# ersa_schematics_analog.net
KiCad netlist of a schematic drawn in Altium Designer
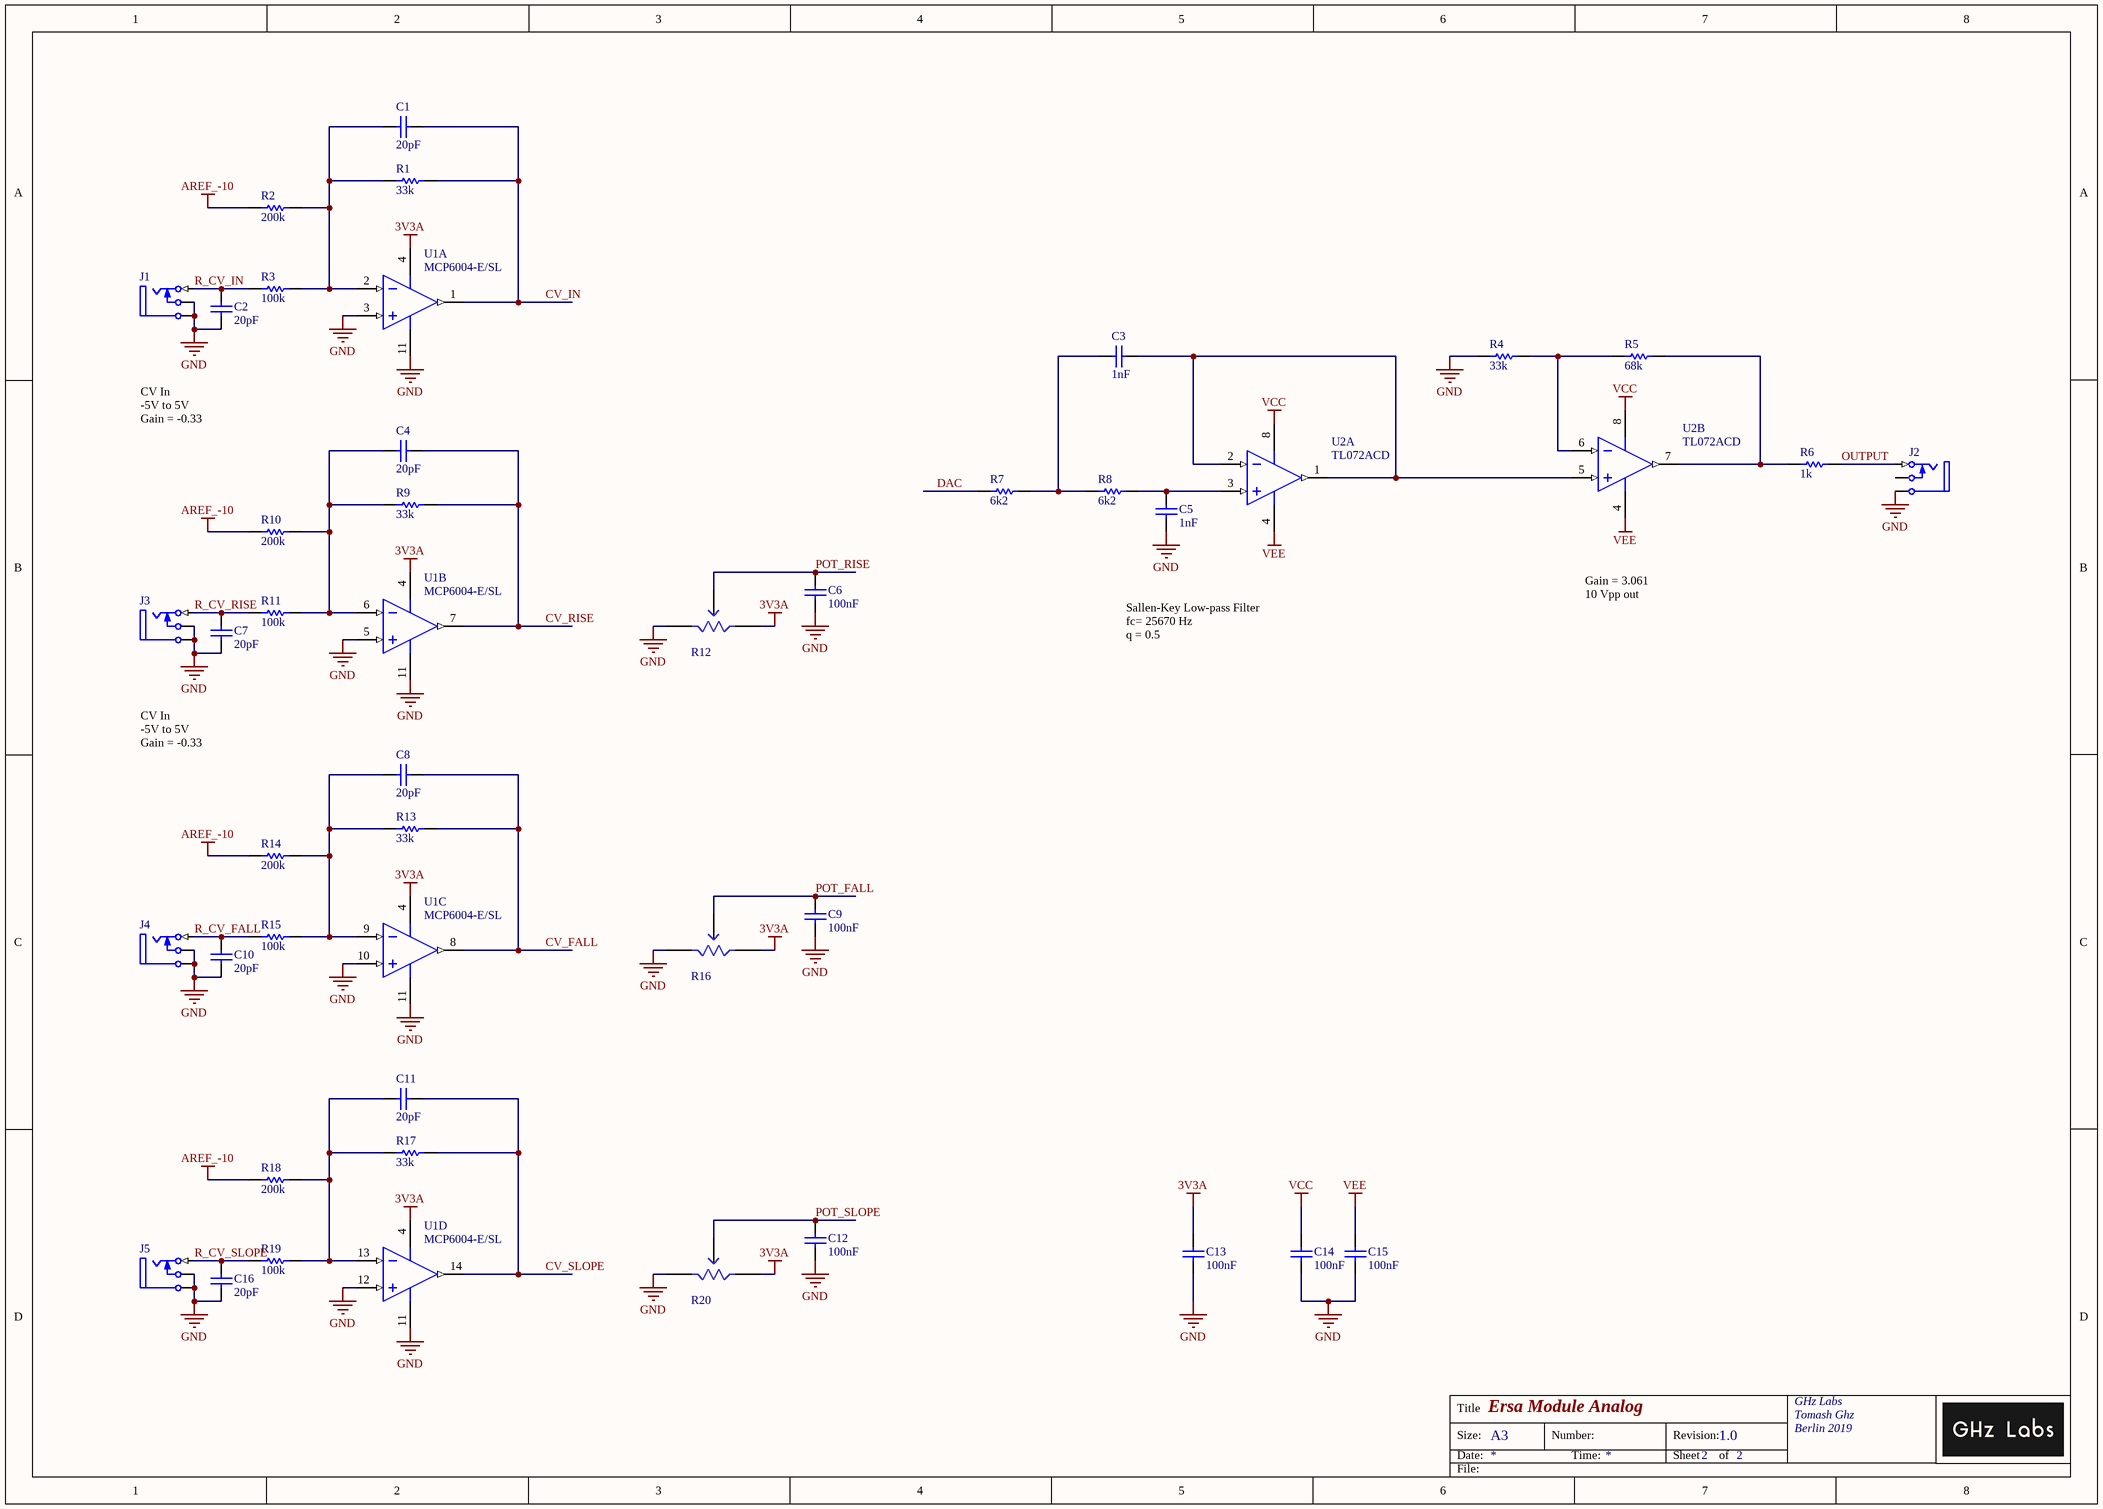
[diagram p0: ersa_schematics_analog.SchDoc]

(export (version "E")
  (design (tool "Eeschema 10.0.6"))
  (components
    (comp (ref "C1")
      (value "20pF")
      (footprint "GHzLabs_Parts:CAPA_0805")
      (description "Capacitor")
      (fields (field (name "PUBLISHER") "Altium Limited"))
      (libsource (lib "GHzLabs_Parts") (part "Cap"))
    )
    (comp (ref "C2")
      (value "20pF")
      (footprint "GHzLabs_Parts:CAPA_0805")
      (description "Capacitor")
      (fields (field (name "PUBLISHER") "Altium Limited"))
      (libsource (lib "GHzLabs_Parts") (part "Cap"))
    )
    (comp (ref "C3")
      (value "1nF")
      (footprint "GHzLabs_Parts:CAPA_0805")
      (description "Capacitor")
      (fields (field (name "PUBLISHER") "Altium Limited"))
      (libsource (lib "GHzLabs_Parts") (part "Cap"))
    )
    (comp (ref "C4")
      (value "20pF")
      (footprint "GHzLabs_Parts:CAPA_0805")
      (description "Capacitor")
      (fields (field (name "PUBLISHER") "Altium Limited"))
      (libsource (lib "GHzLabs_Parts") (part "Cap"))
    )
    (comp (ref "C5")
      (value "1nF")
      (footprint "GHzLabs_Parts:CAPA_0805")
      (description "Capacitor")
      (fields (field (name "PUBLISHER") "Altium Limited"))
      (libsource (lib "GHzLabs_Parts") (part "Cap"))
    )
    (comp (ref "C6")
      (value "100nF")
      (footprint "GHzLabs_Parts:CAPA_0805")
      (description "Capacitor")
      (fields (field (name "PUBLISHER") "Altium Limited"))
      (libsource (lib "Miscellaneous Devices") (part "Cap"))
    )
    (comp (ref "C7")
      (value "20pF")
      (footprint "GHzLabs_Parts:CAPA_0805")
      (description "Capacitor")
      (fields (field (name "PUBLISHER") "Altium Limited"))
      (libsource (lib "GHzLabs_Parts") (part "Cap"))
    )
    (comp (ref "C8")
      (value "20pF")
      (footprint "GHzLabs_Parts:CAPA_0805")
      (description "Capacitor")
      (fields (field (name "PUBLISHER") "Altium Limited"))
      (libsource (lib "GHzLabs_Parts") (part "Cap"))
    )
    (comp (ref "C9")
      (value "100nF")
      (footprint "GHzLabs_Parts:CAPA_0805")
      (description "Capacitor")
      (fields (field (name "PUBLISHER") "Altium Limited"))
      (libsource (lib "Miscellaneous Devices") (part "Cap"))
    )
    (comp (ref "C10")
      (value "20pF")
      (footprint "GHzLabs_Parts:CAPA_0805")
      (description "Capacitor")
      (fields (field (name "PUBLISHER") "Altium Limited"))
      (libsource (lib "GHzLabs_Parts") (part "Cap"))
    )
    (comp (ref "C11")
      (value "20pF")
      (footprint "GHzLabs_Parts:CAPA_0805")
      (description "Capacitor")
      (fields (field (name "PUBLISHER") "Altium Limited"))
      (libsource (lib "GHzLabs_Parts") (part "Cap"))
    )
    (comp (ref "C12")
      (value "100nF")
      (footprint "GHzLabs_Parts:CAPA_0805")
      (description "Capacitor")
      (fields (field (name "PUBLISHER") "Altium Limited"))
      (libsource (lib "Miscellaneous Devices") (part "Cap"))
    )
    (comp (ref "C13")
      (value "100nF")
      (footprint "GHzLabs_Parts:CAPA_0805")
      (description "Capacitor")
      (fields (field (name "PUBLISHER") "Altium Limited"))
      (libsource (lib "Miscellaneous Devices") (part "Cap"))
    )
    (comp (ref "C14")
      (value "100nF")
      (footprint "GHzLabs_Parts:CAPA_0805")
      (description "Capacitor")
      (fields (field (name "PUBLISHER") "Altium Limited"))
      (libsource (lib "Miscellaneous Devices") (part "Cap"))
    )
    (comp (ref "C15")
      (value "100nF")
      (footprint "GHzLabs_Parts:CAPA_0805")
      (description "Capacitor")
      (fields (field (name "PUBLISHER") "Altium Limited"))
      (libsource (lib "Miscellaneous Devices") (part "Cap"))
    )
    (comp (ref "C16")
      (value "20pF")
      (footprint "GHzLabs_Parts:CAPA_0805")
      (description "Capacitor")
      (fields (field (name "PUBLISHER") "Altium Limited"))
      (libsource (lib "GHzLabs_Parts") (part "Cap"))
    )
    (comp (ref "J1")
      (value "Phonejack2 TN")
      (footprint "GHzLabs_Parts:Thonkiconn")
      (description "Jack Socket")
      (fields (field (name "PART") "ACJM-MV35-2S") (field (name "MANUFACTURER") "Amphenol Audio"))
      (libsource (lib "GHzLabs_Parts") (part "Phonejack2 TN"))
    )
    (comp (ref "J2")
      (value "Phonejack2 TN")
      (footprint "GHzLabs_Parts:Thonkiconn")
      (description "Jack Socket")
      (fields (field (name "PART") "ACJM-MV35-2S") (field (name "MANUFACTURER") "Amphenol Audio"))
      (libsource (lib "GHzLabs_Parts") (part "Phonejack2 TN"))
    )
    (comp (ref "J3")
      (value "Phonejack2 TN")
      (footprint "GHzLabs_Parts:Thonkiconn")
      (description "Jack Socket")
      (fields (field (name "PART") "ACJM-MV35-2S") (field (name "MANUFACTURER") "Amphenol Audio"))
      (libsource (lib "GHzLabs_Parts") (part "Phonejack2 TN"))
    )
    (comp (ref "J4")
      (value "Phonejack2 TN")
      (footprint "GHzLabs_Parts:Thonkiconn")
      (description "Jack Socket")
      (fields (field (name "PART") "ACJM-MV35-2S") (field (name "MANUFACTURER") "Amphenol Audio"))
      (libsource (lib "GHzLabs_Parts") (part "Phonejack2 TN"))
    )
    (comp (ref "J5")
      (value "Phonejack2 TN")
      (footprint "GHzLabs_Parts:Thonkiconn")
      (description "Jack Socket")
      (fields (field (name "PART") "ACJM-MV35-2S") (field (name "MANUFACTURER") "Amphenol Audio"))
      (libsource (lib "GHzLabs_Parts") (part "Phonejack2 TN"))
    )
    (comp (ref "R1")
      (value "33k")
      (footprint "GHzLabs_Parts:RES_0805")
      (description "33k 0805")
      (fields (field (name "PARTNUMBER") "RR1220P-105-D") (field (name "MANUFACTURER") "Susumu"))
      (libsource (lib "GHzLabs_Parts") (part "Resistor"))
    )
    (comp (ref "R2")
      (value "200k")
      (footprint "GHzLabs_Parts:RES_0805")
      (description "200k 0805")
      (fields (field (name "PARTNUMBER") "RR1220P-105-D") (field (name "MANUFACTURER") "Susumu"))
      (libsource (lib "GHzLabs_Parts") (part "Resistor"))
    )
    (comp (ref "R3")
      (value "100k")
      (footprint "GHzLabs_Parts:RES_0805")
      (description "100k 0805")
      (fields (field (name "PARTNUMBER") "RR1220P-105-D") (field (name "MANUFACTURER") "Susumu"))
      (libsource (lib "GHzLabs_Parts") (part "Resistor"))
    )
    (comp (ref "R4")
      (value "33k")
      (footprint "GHzLabs_Parts:RES_0805")
      (description "33k 0805")
      (fields (field (name "PARTNUMBER") "RR1220P-105-D") (field (name "MANUFACTURER") "Susumu"))
      (libsource (lib "GHzLabs_Parts") (part "Resistor"))
    )
    (comp (ref "R5")
      (value "68k")
      (footprint "GHzLabs_Parts:RES_0805")
      (description "68k 0805")
      (fields (field (name "PARTNUMBER") "RR1220P-105-D") (field (name "MANUFACTURER") "Susumu"))
      (libsource (lib "GHzLabs_Parts") (part "Resistor"))
    )
    (comp (ref "R6")
      (value "1k")
      (footprint "GHzLabs_Parts:RES_0805")
      (description "1k 0805")
      (fields (field (name "PARTNUMBER") "RR1220P-105-D") (field (name "MANUFACTURER") "Susumu"))
      (libsource (lib "GHzLabs_Parts") (part "Resistor"))
    )
    (comp (ref "R7")
      (value "6k2")
      (footprint "GHzLabs_Parts:RES_0805")
      (description "6k2 0805")
      (fields (field (name "PARTNUMBER") "RR1220P-105-D") (field (name "MANUFACTURER") "Susumu"))
      (libsource (lib "GHzLabs_Parts") (part "Resistor"))
    )
    (comp (ref "R8")
      (value "6k2")
      (footprint "GHzLabs_Parts:RES_0805")
      (description "6k2 0805")
      (fields (field (name "PARTNUMBER") "RR1220P-105-D") (field (name "MANUFACTURER") "Susumu"))
      (libsource (lib "GHzLabs_Parts") (part "Resistor"))
    )
    (comp (ref "R9")
      (value "33k")
      (footprint "GHzLabs_Parts:RES_0805")
      (description "33k 0805")
      (fields (field (name "PARTNUMBER") "RR1220P-105-D") (field (name "MANUFACTURER") "Susumu"))
      (libsource (lib "GHzLabs_Parts") (part "Resistor"))
    )
    (comp (ref "R10")
      (value "200k")
      (footprint "GHzLabs_Parts:RES_0805")
      (description "200k 0805")
      (fields (field (name "PARTNUMBER") "RR1220P-105-D") (field (name "MANUFACTURER") "Susumu"))
      (libsource (lib "GHzLabs_Parts") (part "Resistor"))
    )
    (comp (ref "R11")
      (value "100k")
      (footprint "GHzLabs_Parts:RES_0805")
      (description "100k 0805")
      (fields (field (name "PARTNUMBER") "RR1220P-105-D") (field (name "MANUFACTURER") "Susumu"))
      (libsource (lib "GHzLabs_Parts") (part "Resistor"))
    )
    (comp (ref "R12")
      (value "Potentiometer")
      (footprint "GHzLabs_Parts:POT-ALPHA")
      (fields (field (name "PARTNUMBER") "PTV09A-4020U-B104"))
      (libsource (lib "myParts") (part "Potentiometer"))
    )
    (comp (ref "R13")
      (value "33k")
      (footprint "GHzLabs_Parts:RES_0805")
      (description "33k 0805")
      (fields (field (name "PARTNUMBER") "RR1220P-105-D") (field (name "MANUFACTURER") "Susumu"))
      (libsource (lib "GHzLabs_Parts") (part "Resistor"))
    )
    (comp (ref "R14")
      (value "200k")
      (footprint "GHzLabs_Parts:RES_0805")
      (description "200k 0805")
      (fields (field (name "PARTNUMBER") "RR1220P-105-D") (field (name "MANUFACTURER") "Susumu"))
      (libsource (lib "GHzLabs_Parts") (part "Resistor"))
    )
    (comp (ref "R15")
      (value "100k")
      (footprint "GHzLabs_Parts:RES_0805")
      (description "100k 0805")
      (fields (field (name "PARTNUMBER") "RR1220P-105-D") (field (name "MANUFACTURER") "Susumu"))
      (libsource (lib "GHzLabs_Parts") (part "Resistor"))
    )
    (comp (ref "R16")
      (value "Potentiometer")
      (footprint "GHzLabs_Parts:POT-ALPHA")
      (fields (field (name "PARTNUMBER") "PTV09A-4020U-B104"))
      (libsource (lib "myParts") (part "Potentiometer"))
    )
    (comp (ref "R17")
      (value "33k")
      (footprint "GHzLabs_Parts:RES_0805")
      (description "33k 0805")
      (fields (field (name "PARTNUMBER") "RR1220P-105-D") (field (name "MANUFACTURER") "Susumu"))
      (libsource (lib "GHzLabs_Parts") (part "Resistor"))
    )
    (comp (ref "R18")
      (value "200k")
      (footprint "GHzLabs_Parts:RES_0805")
      (description "200k 0805")
      (fields (field (name "PARTNUMBER") "RR1220P-105-D") (field (name "MANUFACTURER") "Susumu"))
      (libsource (lib "GHzLabs_Parts") (part "Resistor"))
    )
    (comp (ref "R19")
      (value "100k")
      (footprint "GHzLabs_Parts:RES_0805")
      (description "100k 0805")
      (fields (field (name "PARTNUMBER") "RR1220P-105-D") (field (name "MANUFACTURER") "Susumu"))
      (libsource (lib "GHzLabs_Parts") (part "Resistor"))
    )
    (comp (ref "R20")
      (value "Potentiometer")
      (footprint "GHzLabs_Parts:POT-ALPHA")
      (fields (field (name "PARTNUMBER") "PTV09A-4020U-B104"))
      (libsource (lib "myParts") (part "Potentiometer"))
    )
    (comp (ref "U1")
      (value "MCP6004-E/SL")
      (footprint "SOIC-SL14_M")
      (description "1 MHz, Low-Power Operational Amplifier, 14-Pin SOIC, Extended Temperature")
      (fields
        (field (name "PARTNUMBER") "MCP6004T-E/SL")
        (field (name "MANUFACTURER") "Microchip Technology")
        (field (name "PUBLISHER") "Altium Limited")
      )
      (libsource (lib "Microchip Linear Devices") (part "MCP6004-E/SL"))
    )
    (comp (ref "U2")
      (value "TL072ACD")
      (footprint "D0008A_M")
      (fields (field (name "MANUFACTURER") "Texas Instruments"))
      (libsource (lib "Altium Content Vault") (part "CMP-0015-00092-2"))
    )
  )
  (nets
    (net (code "1") (name "/CV_FALL") (class "Default")
      (node (ref "C8") (pin "2") (pinfunction "2_2") (pintype "passive"))
      (node (ref "R13") (pin "1") (pinfunction "1_1") (pintype "passive"))
      (node (ref "U1") (pin "8") (pinfunction "VOUTC_8") (pintype "output"))
    )
    (net (code "2") (name "/CV_IN") (class "Default")
      (node (ref "C1") (pin "2") (pinfunction "2_2") (pintype "passive"))
      (node (ref "R1") (pin "1") (pinfunction "1_1") (pintype "passive"))
      (node (ref "U1") (pin "1") (pinfunction "VOUTA_1") (pintype "output"))
    )
    (net (code "3") (name "/CV_RISE") (class "Default")
      (node (ref "C4") (pin "2") (pinfunction "2_2") (pintype "passive"))
      (node (ref "R9") (pin "1") (pinfunction "1_1") (pintype "passive"))
      (node (ref "U1") (pin "7") (pinfunction "VOUTB_7") (pintype "output"))
    )
    (net (code "4") (name "/CV_SLOPE") (class "Default")
      (node (ref "C11") (pin "2") (pinfunction "2_2") (pintype "passive"))
      (node (ref "R17") (pin "1") (pinfunction "1_1") (pintype "passive"))
      (node (ref "U1") (pin "14") (pinfunction "VOUTD_14") (pintype "output"))
    )
    (net (code "5") (name "/DAC") (class "Default")
      (node (ref "R7") (pin "2") (pinfunction "2_2") (pintype "passive"))
    )
    (net (code "6") (name "/OUTPUT") (class "Default")
      (node (ref "J2") (pin "1") (pinfunction "T_1") (pintype "input"))
      (node (ref "R6") (pin "1") (pinfunction "1_1") (pintype "passive"))
    )
    (net (code "7") (name "/POT_FALL") (class "Default")
      (node (ref "C9") (pin "1") (pinfunction "1_1") (pintype "passive"))
      (node (ref "R16") (pin "2") (pinfunction "2_2") (pintype "power_in"))
    )
    (net (code "8") (name "/POT_RISE") (class "Default")
      (node (ref "C6") (pin "1") (pinfunction "1_1") (pintype "passive"))
      (node (ref "R12") (pin "2") (pinfunction "2_2") (pintype "power_in"))
    )
    (net (code "9") (name "/POT_SLOPE") (class "Default")
      (node (ref "C12") (pin "1") (pinfunction "1_1") (pintype "passive"))
      (node (ref "R20") (pin "2") (pinfunction "2_2") (pintype "power_in"))
    )
    (net (code "10") (name "/R_CV_FALL") (class "Default")
      (node (ref "C10") (pin "2") (pinfunction "2_2") (pintype "passive"))
      (node (ref "J4") (pin "1") (pinfunction "T_1") (pintype "input"))
      (node (ref "R15") (pin "2") (pinfunction "2_2") (pintype "passive"))
    )
    (net (code "11") (name "/R_CV_IN") (class "Default")
      (node (ref "C2") (pin "2") (pinfunction "2_2") (pintype "passive"))
      (node (ref "J1") (pin "1") (pinfunction "T_1") (pintype "input"))
      (node (ref "R3") (pin "2") (pinfunction "2_2") (pintype "passive"))
    )
    (net (code "12") (name "/R_CV_RISE") (class "Default")
      (node (ref "C7") (pin "2") (pinfunction "2_2") (pintype "passive"))
      (node (ref "J3") (pin "1") (pinfunction "T_1") (pintype "input"))
      (node (ref "R11") (pin "2") (pinfunction "2_2") (pintype "passive"))
    )
    (net (code "13") (name "/R_CV_SLOPE") (class "Default")
      (node (ref "C16") (pin "2") (pinfunction "2_2") (pintype "passive"))
      (node (ref "J5") (pin "1") (pinfunction "T_1") (pintype "input"))
      (node (ref "R19") (pin "2") (pinfunction "2_2") (pintype "passive"))
    )
    (net (code "14") (name "3V3A") (class "Default")
      (node (ref "C13") (pin "1") (pinfunction "1_1") (pintype "passive"))
      (node (ref "R12") (pin "3") (pinfunction "3_3") (pintype "power_in"))
      (node (ref "R16") (pin "3") (pinfunction "3_3") (pintype "power_in"))
      (node (ref "R20") (pin "3") (pinfunction "3_3") (pintype "power_in"))
      (node (ref "U1") (pin "4") (pinfunction "VDD_4") (pintype "power_in"))
    )
    (net (code "15") (name "AREF_-10") (class "Default")
      (node (ref "R10") (pin "2") (pinfunction "2_2") (pintype "passive"))
      (node (ref "R14") (pin "2") (pinfunction "2_2") (pintype "passive"))
      (node (ref "R18") (pin "2") (pinfunction "2_2") (pintype "passive"))
      (node (ref "R2") (pin "2") (pinfunction "2_2") (pintype "passive"))
    )
    (net (code "16") (name "GND") (class "Default")
      (node (ref "C10") (pin "1") (pinfunction "1_1") (pintype "passive"))
      (node (ref "C12") (pin "2") (pinfunction "2_2") (pintype "passive"))
      (node (ref "C13") (pin "2") (pinfunction "2_2") (pintype "passive"))
      (node (ref "C14") (pin "2") (pinfunction "2_2") (pintype "passive"))
      (node (ref "C15") (pin "2") (pinfunction "2_2") (pintype "passive"))
      (node (ref "C16") (pin "1") (pinfunction "1_1") (pintype "passive"))
      (node (ref "C2") (pin "1") (pinfunction "1_1") (pintype "passive"))
      (node (ref "C5") (pin "1") (pinfunction "1_1") (pintype "passive"))
      (node (ref "C6") (pin "2") (pinfunction "2_2") (pintype "passive"))
      (node (ref "C7") (pin "1") (pinfunction "1_1") (pintype "passive"))
      (node (ref "C9") (pin "2") (pinfunction "2_2") (pintype "passive"))
      (node (ref "J1") (pin "2") (pinfunction "TN_2") (pintype "passive"))
      (node (ref "J1") (pin "5") (pinfunction "S_5") (pintype "power_in"))
      (node (ref "J2") (pin "5") (pinfunction "S_5") (pintype "power_in"))
      (node (ref "J3") (pin "2") (pinfunction "TN_2") (pintype "passive"))
      (node (ref "J3") (pin "5") (pinfunction "S_5") (pintype "power_in"))
      (node (ref "J4") (pin "2") (pinfunction "TN_2") (pintype "passive"))
      (node (ref "J4") (pin "5") (pinfunction "S_5") (pintype "power_in"))
      (node (ref "J5") (pin "2") (pinfunction "TN_2") (pintype "passive"))
      (node (ref "J5") (pin "5") (pinfunction "S_5") (pintype "power_in"))
      (node (ref "R12") (pin "1") (pinfunction "1_1") (pintype "power_in"))
      (node (ref "R16") (pin "1") (pinfunction "1_1") (pintype "power_in"))
      (node (ref "R20") (pin "1") (pinfunction "1_1") (pintype "power_in"))
      (node (ref "R4") (pin "2") (pinfunction "2_2") (pintype "passive"))
      (node (ref "U1") (pin "10") (pinfunction "VINC+_10") (pintype "input"))
      (node (ref "U1") (pin "11") (pinfunction "VSS_11") (pintype "power_in"))
      (node (ref "U1") (pin "12") (pinfunction "VIND+_12") (pintype "input"))
      (node (ref "U1") (pin "3") (pinfunction "VINA+_3") (pintype "input"))
      (node (ref "U1") (pin "5") (pinfunction "VINB+_5") (pintype "input"))
    )
    (net (code "17") (name "Net-(C3-Pad1)") (class "Default")
      (node (ref "C3") (pin "1") (pinfunction "1_1") (pintype "passive"))
      (node (ref "R7") (pin "1") (pinfunction "1_1") (pintype "passive"))
      (node (ref "R8") (pin "2") (pinfunction "2_2") (pintype "passive"))
    )
    (net (code "18") (name "Net-(U1A-VINA-)") (class "Default")
      (node (ref "C1") (pin "1") (pinfunction "1_1") (pintype "passive"))
      (node (ref "R1") (pin "2") (pinfunction "2_2") (pintype "passive"))
      (node (ref "R2") (pin "1") (pinfunction "1_1") (pintype "passive"))
      (node (ref "R3") (pin "1") (pinfunction "1_1") (pintype "passive"))
      (node (ref "U1") (pin "2") (pinfunction "VINA-_2") (pintype "input"))
    )
    (net (code "19") (name "Net-(U1B-VINB-)") (class "Default")
      (node (ref "C4") (pin "1") (pinfunction "1_1") (pintype "passive"))
      (node (ref "R10") (pin "1") (pinfunction "1_1") (pintype "passive"))
      (node (ref "R11") (pin "1") (pinfunction "1_1") (pintype "passive"))
      (node (ref "R9") (pin "2") (pinfunction "2_2") (pintype "passive"))
      (node (ref "U1") (pin "6") (pinfunction "VINB-_6") (pintype "input"))
    )
    (net (code "20") (name "Net-(U1C-VINC-)") (class "Default")
      (node (ref "C8") (pin "1") (pinfunction "1_1") (pintype "passive"))
      (node (ref "R13") (pin "2") (pinfunction "2_2") (pintype "passive"))
      (node (ref "R14") (pin "1") (pinfunction "1_1") (pintype "passive"))
      (node (ref "R15") (pin "1") (pinfunction "1_1") (pintype "passive"))
      (node (ref "U1") (pin "9") (pinfunction "VINC-_9") (pintype "input"))
    )
    (net (code "21") (name "Net-(U1D-VIND-)") (class "Default")
      (node (ref "C11") (pin "1") (pinfunction "1_1") (pintype "passive"))
      (node (ref "R17") (pin "2") (pinfunction "2_2") (pintype "passive"))
      (node (ref "R18") (pin "1") (pinfunction "1_1") (pintype "passive"))
      (node (ref "R19") (pin "1") (pinfunction "1_1") (pintype "passive"))
      (node (ref "U1") (pin "13") (pinfunction "VIND-_13") (pintype "input"))
    )
    (net (code "22") (name "Net-(U2A-IN1+)") (class "Default")
      (node (ref "C5") (pin "2") (pinfunction "2_2") (pintype "passive"))
      (node (ref "R8") (pin "1") (pinfunction "1_1") (pintype "passive"))
      (node (ref "U2") (pin "3") (pinfunction "IN1+_3") (pintype "input"))
    )
    (net (code "23") (name "Net-(U2A-IN1-)") (class "Default")
      (node (ref "C3") (pin "2") (pinfunction "2_2") (pintype "passive"))
      (node (ref "U2") (pin "1") (pinfunction "OUT1_1") (pintype "output"))
      (node (ref "U2") (pin "2") (pinfunction "IN1-_2") (pintype "input"))
      (node (ref "U2") (pin "5") (pinfunction "IN2+_5") (pintype "input"))
    )
    (net (code "24") (name "Net-(U2B-IN2-)") (class "Default")
      (node (ref "R4") (pin "1") (pinfunction "1_1") (pintype "passive"))
      (node (ref "R5") (pin "2") (pinfunction "2_2") (pintype "passive"))
      (node (ref "U2") (pin "6") (pinfunction "IN2-_6") (pintype "input"))
    )
    (net (code "25") (name "Net-(U2B-OUT2)") (class "Default")
      (node (ref "R5") (pin "1") (pinfunction "1_1") (pintype "passive"))
      (node (ref "R6") (pin "2") (pinfunction "2_2") (pintype "passive"))
      (node (ref "U2") (pin "7") (pinfunction "OUT2_7") (pintype "output"))
    )
    (net (code "26") (name "VCC") (class "Default")
      (node (ref "C14") (pin "1") (pinfunction "1_1") (pintype "passive"))
      (node (ref "U2") (pin "8") (pinfunction "VCC+_8") (pintype "power_in"))
    )
    (net (code "27") (name "VEE") (class "Default")
      (node (ref "C15") (pin "1") (pinfunction "1_1") (pintype "passive"))
      (node (ref "U2") (pin "4") (pinfunction "VCC-_4") (pintype "power_in"))
    )
    (net (code "28") (name "unconnected-(J2-TN-Pad2)") (class "Default")
      (node (ref "J2") (pin "2") (pinfunction "TN_2") (pintype "passive"))
    )
  )
)
